# Master_System_II_Rgb.net
KiCad netlist of a schematic drawn in EAGLE
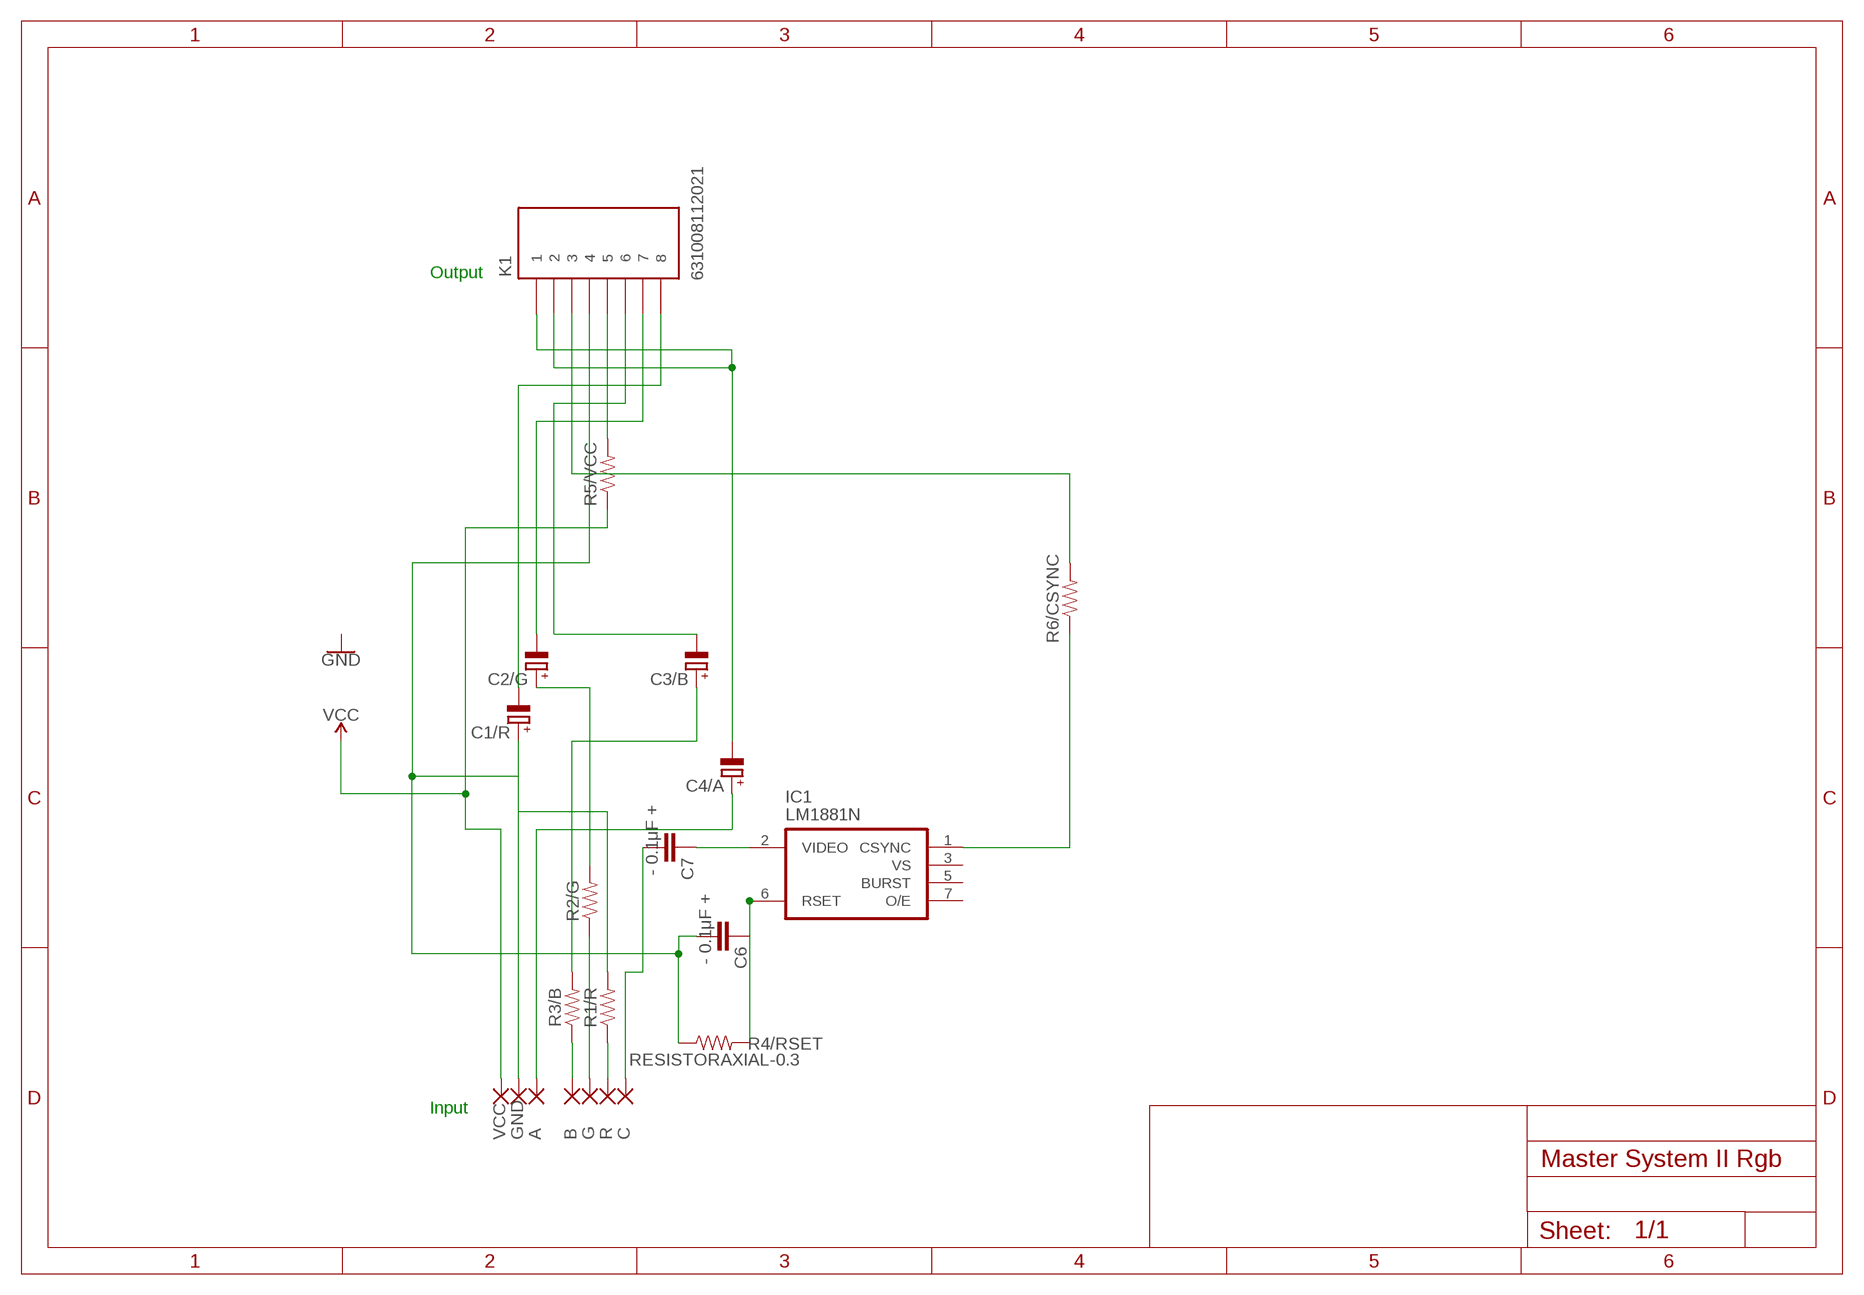
[diagram p0: schematic, sheet 1]

(export (version "E")
  (design (tool "Eeschema 10.0.6"))
  (components
    (comp (ref "A")
      (value "WIREPADSMD2,54-5,08")
      (footprint "eagle-import:SMD2,54-5,08")
      (libsource (lib "eagle-import") (part "WIREPADSMD2,54-5,08"))
    )
    (comp (ref "B")
      (value "WIREPADSMD2,54-5,08")
      (footprint "eagle-import:SMD2,54-5,08")
      (libsource (lib "eagle-import") (part "WIREPADSMD2,54-5,08"))
    )
    (comp (ref "C")
      (value "WIREPADSMD2,54-5,08")
      (footprint "eagle-import:SMD2,54-5,08")
      (libsource (lib "eagle-import") (part "WIREPADSMD2,54-5,08"))
    )
    (comp (ref "C1/R")
      (value "CPOL-EUE2.5-6")
      (footprint "eagle-import:E2,5-6")
      (libsource (lib "eagle-import") (part "CPOL-EUE2.5-6"))
    )
    (comp (ref "C2/G")
      (value "CPOL-EUE2.5-6")
      (footprint "eagle-import:E2,5-6")
      (libsource (lib "eagle-import") (part "CPOL-EUE2.5-6"))
    )
    (comp (ref "C3/B")
      (value "CPOL-EUE2.5-6")
      (footprint "eagle-import:E2,5-6")
      (libsource (lib "eagle-import") (part "CPOL-EUE2.5-6"))
    )
    (comp (ref "C4/A")
      (value "CPOL-EUE2.5-6")
      (footprint "eagle-import:E2,5-6")
      (libsource (lib "eagle-import") (part "CPOL-EUE2.5-6"))
    )
    (comp (ref "C6")
      (value "- 0.1μF +")
      (footprint "eagle-import:CAP-PTH-2.54")
      (libsource (lib "eagle-import") (part "22PF-PTH-2.54MM-200V-5%"))
    )
    (comp (ref "C7")
      (value "- 0.1μF +")
      (footprint "eagle-import:CAP-PTH-2.54")
      (libsource (lib "eagle-import") (part "22PF-PTH-2.54MM-200V-5%"))
    )
    (comp (ref "G")
      (value "WIREPADSMD2,54-5,08")
      (footprint "eagle-import:SMD2,54-5,08")
      (libsource (lib "eagle-import") (part "WIREPADSMD2,54-5,08"))
    )
    (comp (ref "GND")
      (value "WIREPADSMD2,54-5,08")
      (footprint "eagle-import:SMD2,54-5,08")
      (libsource (lib "eagle-import") (part "WIREPADSMD2,54-5,08"))
    )
    (comp (ref "IC1")
      (value "LM1881N")
      (footprint "eagle-import:DIL08")
      (libsource (lib "eagle-import") (part "LM1881N"))
    )
    (comp (ref "K1")
      (value "631008112021")
      (footprint "eagle-import:631008112021")
      (libsource (lib "eagle-import") (part "631008112021"))
    )
    (comp (ref "R")
      (value "WIREPADSMD2,54-5,08")
      (footprint "eagle-import:SMD2,54-5,08")
      (libsource (lib "eagle-import") (part "WIREPADSMD2,54-5,08"))
    )
    (comp (ref "R1/R")
      (value "RESISTORAXIAL-0.3")
      (footprint "eagle-import:AXIAL-0.3")
      (libsource (lib "eagle-import") (part "RESISTORAXIAL-0.3"))
    )
    (comp (ref "R2/G")
      (value "RESISTORAXIAL-0.3")
      (footprint "eagle-import:AXIAL-0.3")
      (libsource (lib "eagle-import") (part "RESISTORAXIAL-0.3"))
    )
    (comp (ref "R3/B")
      (value "RESISTORAXIAL-0.3")
      (footprint "eagle-import:AXIAL-0.3")
      (libsource (lib "eagle-import") (part "RESISTORAXIAL-0.3"))
    )
    (comp (ref "R4/RSET")
      (value "RESISTORAXIAL-0.3")
      (footprint "eagle-import:AXIAL-0.3")
      (libsource (lib "eagle-import") (part "RESISTORAXIAL-0.3"))
    )
    (comp (ref "R5/VCC")
      (value "RESISTORAXIAL-0.3")
      (footprint "eagle-import:AXIAL-0.3")
      (libsource (lib "eagle-import") (part "RESISTORAXIAL-0.3"))
    )
    (comp (ref "R6/CSYNC")
      (value "RESISTORAXIAL-0.3")
      (footprint "eagle-import:AXIAL-0.3")
      (libsource (lib "eagle-import") (part "RESISTORAXIAL-0.3"))
    )
    (comp (ref "VCC")
      (value "WIREPADSMD2,54-5,08")
      (footprint "eagle-import:SMD2,54-5,08")
      (libsource (lib "eagle-import") (part "WIREPADSMD2,54-5,08"))
    )
  )
  (nets
    (net (code "2") (name "Net-(A-P)") (class "Default")
      (node (ref "A") (pin "1") (pinfunction "P_1") (pintype "passive"))
      (node (ref "C4/A") (pin "+") (pinfunction "+_+") (pintype "passive"))
    )
    (net (code "3") (name "Net-(B-P)") (class "Default")
      (node (ref "B") (pin "1") (pinfunction "P_1") (pintype "passive"))
      (node (ref "R3/B") (pin "P$1") (pinfunction "1_P$1") (pintype "passive"))
    )
    (net (code "4") (name "Net-(C-P)") (class "Default")
      (node (ref "C") (pin "1") (pinfunction "P_1") (pintype "passive"))
      (node (ref "C7") (pin "2") (pinfunction "2_2") (pintype "passive"))
    )
    (net (code "5") (name "Net-(G-P)") (class "Default")
      (node (ref "G") (pin "1") (pinfunction "P_1") (pintype "passive"))
      (node (ref "R2/G") (pin "P$1") (pinfunction "1_P$1") (pintype "passive"))
    )
    (net (code "6") (name "Net-(GND-P)") (class "Default")
      (node (ref "C6") (pin "2") (pinfunction "2_2") (pintype "passive"))
      (node (ref "GND") (pin "1") (pinfunction "P_1") (pintype "passive"))
      (node (ref "K1") (pin "7") (pinfunction "4_7") (pintype "passive"))
      (node (ref "R4/RSET") (pin "P$1") (pinfunction "1_P$1") (pintype "passive"))
    )
    (net (code "7") (name "Net-(IC1A-CSYNC)") (class "Default")
      (node (ref "IC1") (pin "1") (pinfunction "CSYNC_1") (pintype "output"))
      (node (ref "R6/CSYNC") (pin "P$1") (pinfunction "1_P$1") (pintype "passive"))
    )
    (net (code "8") (name "Net-(IC1A-RSET)") (class "Default")
      (node (ref "C6") (pin "1") (pinfunction "1_1") (pintype "passive"))
      (node (ref "IC1") (pin "6") (pinfunction "RSET_6") (pintype "passive"))
      (node (ref "R4/RSET") (pin "P$2") (pinfunction "2_P$2") (pintype "passive"))
    )
    (net (code "9") (name "Net-(IC1A-VIDEO)") (class "Default")
      (node (ref "C7") (pin "1") (pinfunction "1_1") (pintype "passive"))
      (node (ref "IC1") (pin "2") (pinfunction "VIDEO_2") (pintype "input"))
    )
    (net (code "10") (name "Net-(K1-1)") (class "Default")
      (node (ref "C4/A") (pin "-") (pinfunction "-_-") (pintype "passive"))
      (node (ref "K1") (pin "1") (pinfunction "2_1") (pintype "passive"))
      (node (ref "K1") (pin "2") (pinfunction "1_2") (pintype "passive"))
    )
    (net (code "11") (name "Net-(K1-3)") (class "Default")
      (node (ref "K1") (pin "5") (pinfunction "3_5") (pintype "passive"))
      (node (ref "R6/CSYNC") (pin "P$2") (pinfunction "2_P$2") (pintype "passive"))
    )
    (net (code "12") (name "Net-(K1-5)") (class "Default")
      (node (ref "K1") (pin "3") (pinfunction "5_3") (pintype "passive"))
      (node (ref "R5/VCC") (pin "P$2") (pinfunction "2_P$2") (pintype "passive"))
    )
    (net (code "13") (name "Net-(K1-6)") (class "Default")
      (node (ref "C3/B") (pin "-") (pinfunction "-_-") (pintype "passive"))
      (node (ref "K1") (pin "8") (pinfunction "6_8") (pintype "passive"))
    )
    (net (code "14") (name "Net-(K1-7)") (class "Default")
      (node (ref "C2/G") (pin "-") (pinfunction "-_-") (pintype "passive"))
      (node (ref "K1") (pin "4") (pinfunction "7_4") (pintype "passive"))
    )
    (net (code "15") (name "Net-(K1-8)") (class "Default")
      (node (ref "C1/R") (pin "-") (pinfunction "-_-") (pintype "passive"))
      (node (ref "K1") (pin "6") (pinfunction "8_6") (pintype "passive"))
    )
    (net (code "16") (name "Net-(R-P)") (class "Default")
      (node (ref "R") (pin "1") (pinfunction "P_1") (pintype "passive"))
      (node (ref "R1/R") (pin "P$1") (pinfunction "1_P$1") (pintype "passive"))
    )
    (net (code "17") (name "Net-(R1/R-2)") (class "Default")
      (node (ref "C1/R") (pin "+") (pinfunction "+_+") (pintype "passive"))
      (node (ref "R1/R") (pin "P$2") (pinfunction "2_P$2") (pintype "passive"))
    )
    (net (code "18") (name "Net-(R2/G-2)") (class "Default")
      (node (ref "C2/G") (pin "+") (pinfunction "+_+") (pintype "passive"))
      (node (ref "R2/G") (pin "P$2") (pinfunction "2_P$2") (pintype "passive"))
    )
    (net (code "19") (name "Net-(R3/B-2)") (class "Default")
      (node (ref "C3/B") (pin "+") (pinfunction "+_+") (pintype "passive"))
      (node (ref "R3/B") (pin "P$2") (pinfunction "2_P$2") (pintype "passive"))
    )
    (net (code "20") (name "VCC") (class "Default")
      (node (ref "R5/VCC") (pin "P$1") (pinfunction "1_P$1") (pintype "passive"))
      (node (ref "VCC") (pin "1") (pinfunction "P_1") (pintype "passive"))
    )
    (net (code "21") (name "unconnected-(IC1A-BURST-Pad5)") (class "Default")
      (node (ref "IC1") (pin "5") (pinfunction "BURST_5") (pintype "output"))
    )
    (net (code "22") (name "unconnected-(IC1A-O{slash}E-Pad7)") (class "Default")
      (node (ref "IC1") (pin "7") (pinfunction "O/E_7") (pintype "output"))
    )
    (net (code "23") (name "unconnected-(IC1A-VS-Pad3)") (class "Default")
      (node (ref "IC1") (pin "3") (pinfunction "VS_3") (pintype "output"))
    )
  )
)
